# DEC_1_0.net
KiCad netlist of a schematic drawn in EAGLE
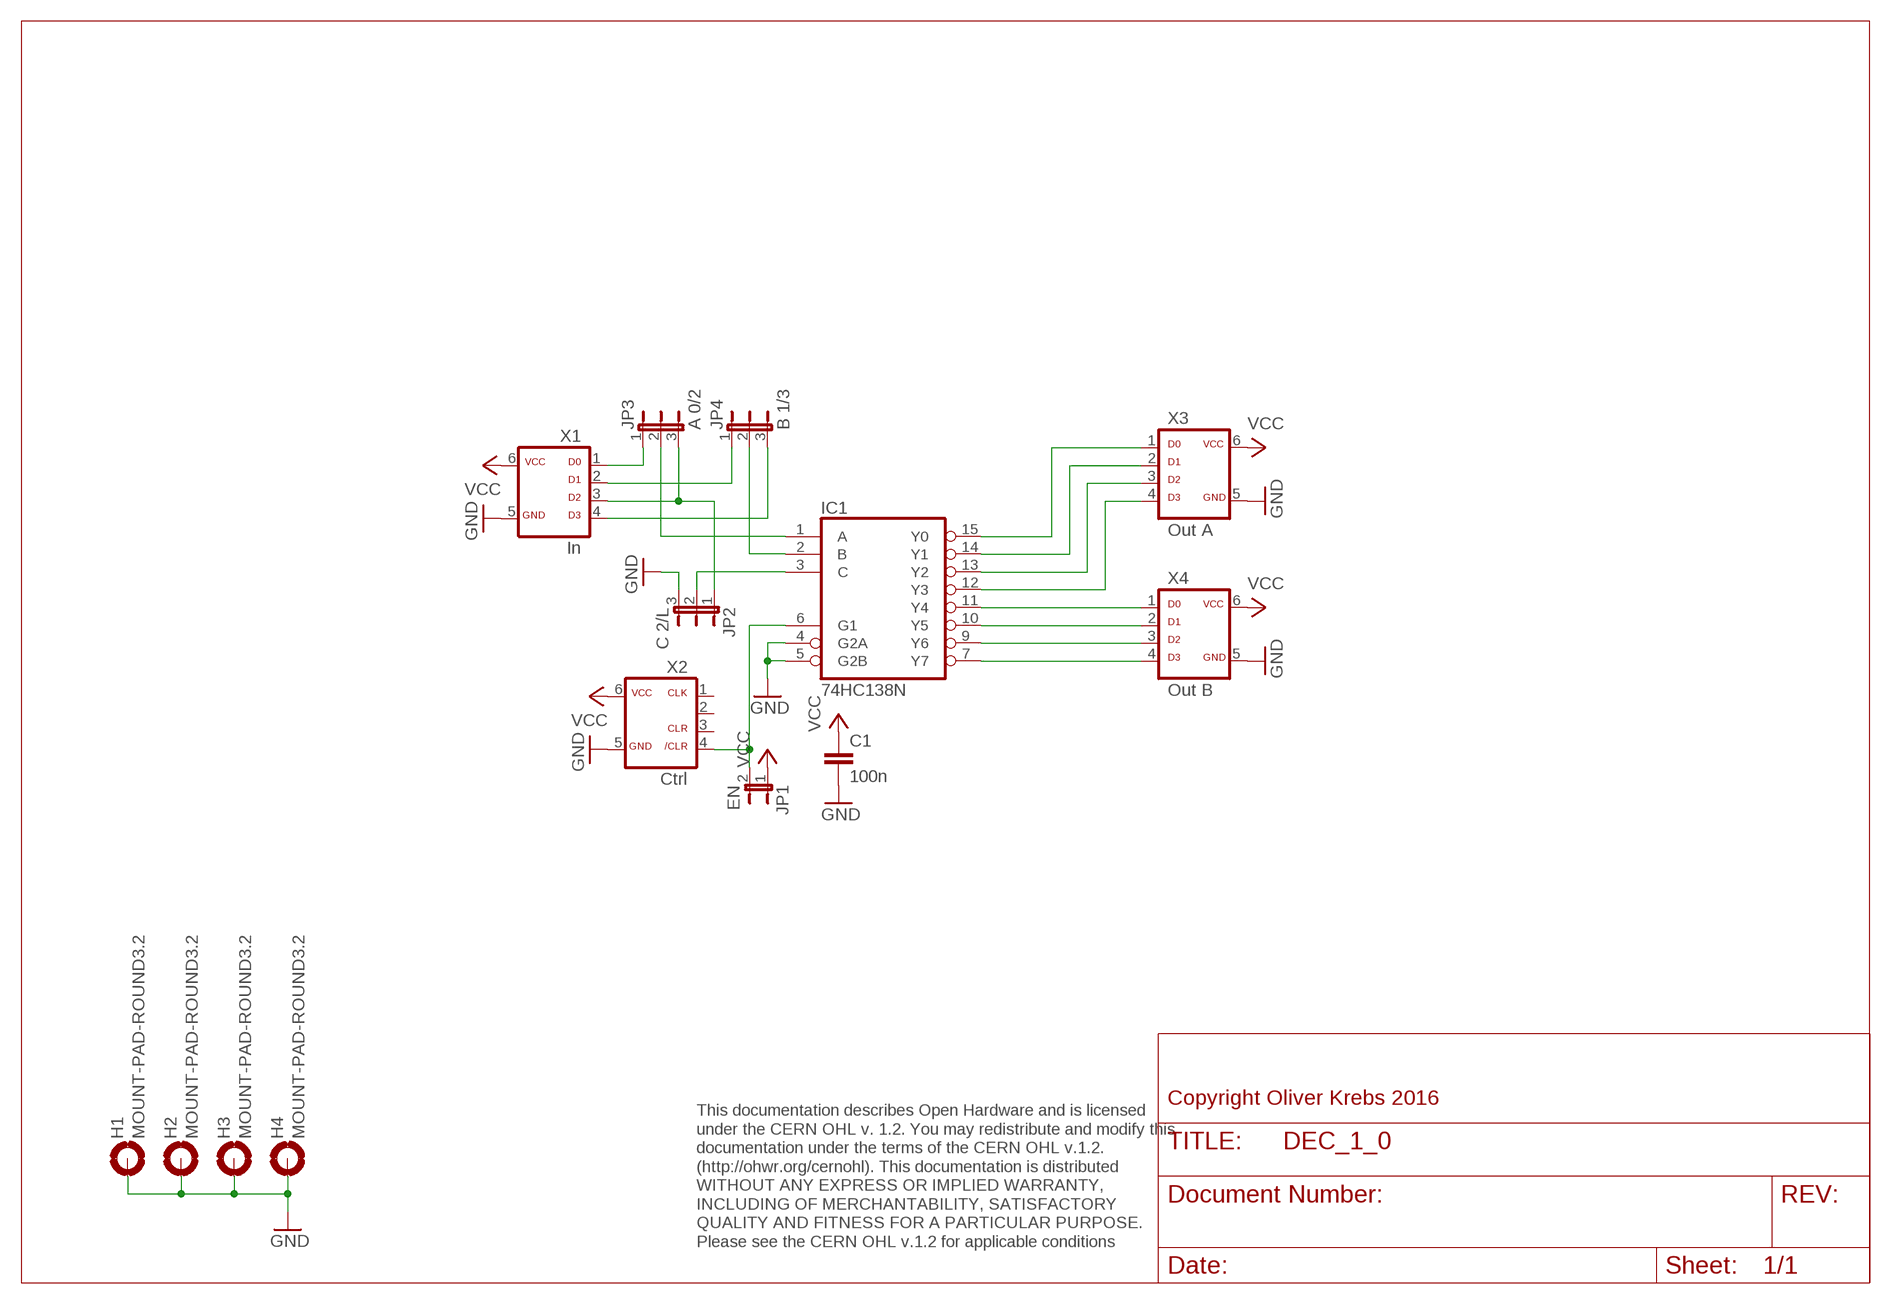
[diagram p0: schematic, sheet 1]

(export (version "E")
  (design (tool "Eeschema 10.0.6"))
  (components
    (comp (ref "C1")
      (value "100n")
      (footprint "eagle-import:C050-025X075")
      (libsource (lib "eagle-import") (part "C-EU050-025X075"))
    )
    (comp (ref "H1")
      (value "MOUNT-PAD-ROUND3.2")
      (footprint "eagle-import:3,2-PAD")
      (libsource (lib "eagle-import") (part "MOUNT-PAD-ROUND3.2"))
    )
    (comp (ref "H2")
      (value "MOUNT-PAD-ROUND3.2")
      (footprint "eagle-import:3,2-PAD")
      (libsource (lib "eagle-import") (part "MOUNT-PAD-ROUND3.2"))
    )
    (comp (ref "H3")
      (value "MOUNT-PAD-ROUND3.2")
      (footprint "eagle-import:3,2-PAD")
      (libsource (lib "eagle-import") (part "MOUNT-PAD-ROUND3.2"))
    )
    (comp (ref "H4")
      (value "MOUNT-PAD-ROUND3.2")
      (footprint "eagle-import:3,2-PAD")
      (libsource (lib "eagle-import") (part "MOUNT-PAD-ROUND3.2"))
    )
    (comp (ref "IC1")
      (value "74HC138N")
      (footprint "eagle-import:DIL16")
      (libsource (lib "eagle-import") (part "74138NHC"))
    )
    (comp (ref "JP1")
      (value "EN")
      (footprint "eagle-import:JP1")
      (libsource (lib "eagle-import") (part "JP1E"))
    )
    (comp (ref "JP2")
      (value "C 2/L")
      (footprint "eagle-import:JP2")
      (libsource (lib "eagle-import") (part "JP2E"))
    )
    (comp (ref "JP3")
      (value "A 0/2")
      (footprint "eagle-import:JP2")
      (libsource (lib "eagle-import") (part "JP2E"))
    )
    (comp (ref "JP4")
      (value "B 1/3")
      (footprint "eagle-import:JP2")
      (libsource (lib "eagle-import") (part "JP2E"))
    )
    (comp (ref "X1")
      (value "In")
      (footprint "eagle-import:ML-6")
      (libsource (lib "eagle-import") (part "ML6D"))
    )
    (comp (ref "X2")
      (value "Ctrl")
      (footprint "eagle-import:ML-6")
      (libsource (lib "eagle-import") (part "ML6C"))
    )
    (comp (ref "X3")
      (value "Out A")
      (footprint "eagle-import:ML-6")
      (libsource (lib "eagle-import") (part "ML6D"))
    )
    (comp (ref "X4")
      (value "Out B")
      (footprint "eagle-import:ML-6")
      (libsource (lib "eagle-import") (part "ML6D"))
    )
  )
  (nets
    (net (code "1") (name "GND") (class "Default")
      (node (ref "C1") (pin "2") (pinfunction "2_2") (pintype "passive"))
      (node (ref "H1") (pin "B3,2") (pinfunction "MOUNT_B3,2") (pintype "passive"))
      (node (ref "H2") (pin "B3,2") (pinfunction "MOUNT_B3,2") (pintype "passive"))
      (node (ref "H3") (pin "B3,2") (pinfunction "MOUNT_B3,2") (pintype "passive"))
      (node (ref "H4") (pin "B3,2") (pinfunction "MOUNT_B3,2") (pintype "passive"))
      (node (ref "IC1") (pin "4") (pinfunction "G2A_4") (pintype "input"))
      (node (ref "IC1") (pin "5") (pinfunction "G2B_5") (pintype "input"))
      (node (ref "JP2") (pin "3") (pinfunction "3_3") (pintype "passive"))
      (node (ref "X1") (pin "5") (pinfunction "5_5") (pintype "passive"))
      (node (ref "X2") (pin "5") (pinfunction "5_5") (pintype "passive"))
      (node (ref "X3") (pin "5") (pinfunction "5_5") (pintype "passive"))
      (node (ref "X4") (pin "5") (pinfunction "5_5") (pintype "passive"))
    )
    (net (code "2") (name "Net-(IC1A-A)") (class "Default")
      (node (ref "IC1") (pin "1") (pinfunction "A_1") (pintype "input"))
      (node (ref "JP3") (pin "2") (pinfunction "2_2") (pintype "passive"))
    )
    (net (code "3") (name "Net-(IC1A-B)") (class "Default")
      (node (ref "IC1") (pin "2") (pinfunction "B_2") (pintype "input"))
      (node (ref "JP4") (pin "2") (pinfunction "2_2") (pintype "passive"))
    )
    (net (code "4") (name "Net-(IC1A-C)") (class "Default")
      (node (ref "IC1") (pin "3") (pinfunction "C_3") (pintype "input"))
      (node (ref "JP2") (pin "2") (pinfunction "2_2") (pintype "passive"))
    )
    (net (code "5") (name "Net-(IC1A-G1)") (class "Default")
      (node (ref "IC1") (pin "6") (pinfunction "G1_6") (pintype "input"))
      (node (ref "JP1") (pin "2") (pinfunction "2_2") (pintype "passive"))
      (node (ref "X2") (pin "4") (pinfunction "4_4") (pintype "passive"))
    )
    (net (code "6") (name "Net-(IC1A-Y0)") (class "Default")
      (node (ref "IC1") (pin "15") (pinfunction "Y0_15") (pintype "output"))
      (node (ref "X3") (pin "1") (pinfunction "1_1") (pintype "passive"))
    )
    (net (code "7") (name "Net-(IC1A-Y1)") (class "Default")
      (node (ref "IC1") (pin "14") (pinfunction "Y1_14") (pintype "output"))
      (node (ref "X3") (pin "2") (pinfunction "2_2") (pintype "passive"))
    )
    (net (code "8") (name "Net-(IC1A-Y2)") (class "Default")
      (node (ref "IC1") (pin "13") (pinfunction "Y2_13") (pintype "output"))
      (node (ref "X3") (pin "3") (pinfunction "3_3") (pintype "passive"))
    )
    (net (code "9") (name "Net-(IC1A-Y3)") (class "Default")
      (node (ref "IC1") (pin "12") (pinfunction "Y3_12") (pintype "output"))
      (node (ref "X3") (pin "4") (pinfunction "4_4") (pintype "passive"))
    )
    (net (code "10") (name "Net-(IC1A-Y4)") (class "Default")
      (node (ref "IC1") (pin "11") (pinfunction "Y4_11") (pintype "output"))
      (node (ref "X4") (pin "1") (pinfunction "1_1") (pintype "passive"))
    )
    (net (code "11") (name "Net-(IC1A-Y5)") (class "Default")
      (node (ref "IC1") (pin "10") (pinfunction "Y5_10") (pintype "output"))
      (node (ref "X4") (pin "2") (pinfunction "2_2") (pintype "passive"))
    )
    (net (code "12") (name "Net-(IC1A-Y6)") (class "Default")
      (node (ref "IC1") (pin "9") (pinfunction "Y6_9") (pintype "output"))
      (node (ref "X4") (pin "3") (pinfunction "3_3") (pintype "passive"))
    )
    (net (code "13") (name "Net-(IC1A-Y7)") (class "Default")
      (node (ref "IC1") (pin "7") (pinfunction "Y7_7") (pintype "output"))
      (node (ref "X4") (pin "4") (pinfunction "4_4") (pintype "passive"))
    )
    (net (code "14") (name "Net-(JP2-Pad1)") (class "Default")
      (node (ref "JP2") (pin "1") (pinfunction "1_1") (pintype "passive"))
      (node (ref "JP3") (pin "3") (pinfunction "3_3") (pintype "passive"))
      (node (ref "X1") (pin "3") (pinfunction "3_3") (pintype "passive"))
    )
    (net (code "15") (name "Net-(JP3-Pad1)") (class "Default")
      (node (ref "JP3") (pin "1") (pinfunction "1_1") (pintype "passive"))
      (node (ref "X1") (pin "1") (pinfunction "1_1") (pintype "passive"))
    )
    (net (code "16") (name "Net-(JP4-Pad1)") (class "Default")
      (node (ref "JP4") (pin "1") (pinfunction "1_1") (pintype "passive"))
      (node (ref "X1") (pin "2") (pinfunction "2_2") (pintype "passive"))
    )
    (net (code "17") (name "Net-(JP4-Pad3)") (class "Default")
      (node (ref "JP4") (pin "3") (pinfunction "3_3") (pintype "passive"))
      (node (ref "X1") (pin "4") (pinfunction "4_4") (pintype "passive"))
    )
    (net (code "18") (name "VCC") (class "Default")
      (node (ref "C1") (pin "1") (pinfunction "1_1") (pintype "passive"))
      (node (ref "JP1") (pin "1") (pinfunction "1_1") (pintype "passive"))
      (node (ref "X1") (pin "6") (pinfunction "6_6") (pintype "passive"))
      (node (ref "X2") (pin "6") (pinfunction "6_6") (pintype "passive"))
      (node (ref "X3") (pin "6") (pinfunction "6_6") (pintype "passive"))
      (node (ref "X4") (pin "6") (pinfunction "6_6") (pintype "passive"))
    )
    (net (code "19") (name "unconnected-(X2-Pad1)") (class "Default")
      (node (ref "X2") (pin "1") (pinfunction "1_1") (pintype "passive"))
    )
    (net (code "20") (name "unconnected-(X2-Pad2)") (class "Default")
      (node (ref "X2") (pin "2") (pinfunction "2_2") (pintype "passive"))
    )
    (net (code "21") (name "unconnected-(X2-Pad3)") (class "Default")
      (node (ref "X2") (pin "3") (pinfunction "3_3") (pintype "passive"))
    )
  )
)
